# untitled.net
KiCad netlist of a schematic drawn in EAGLE
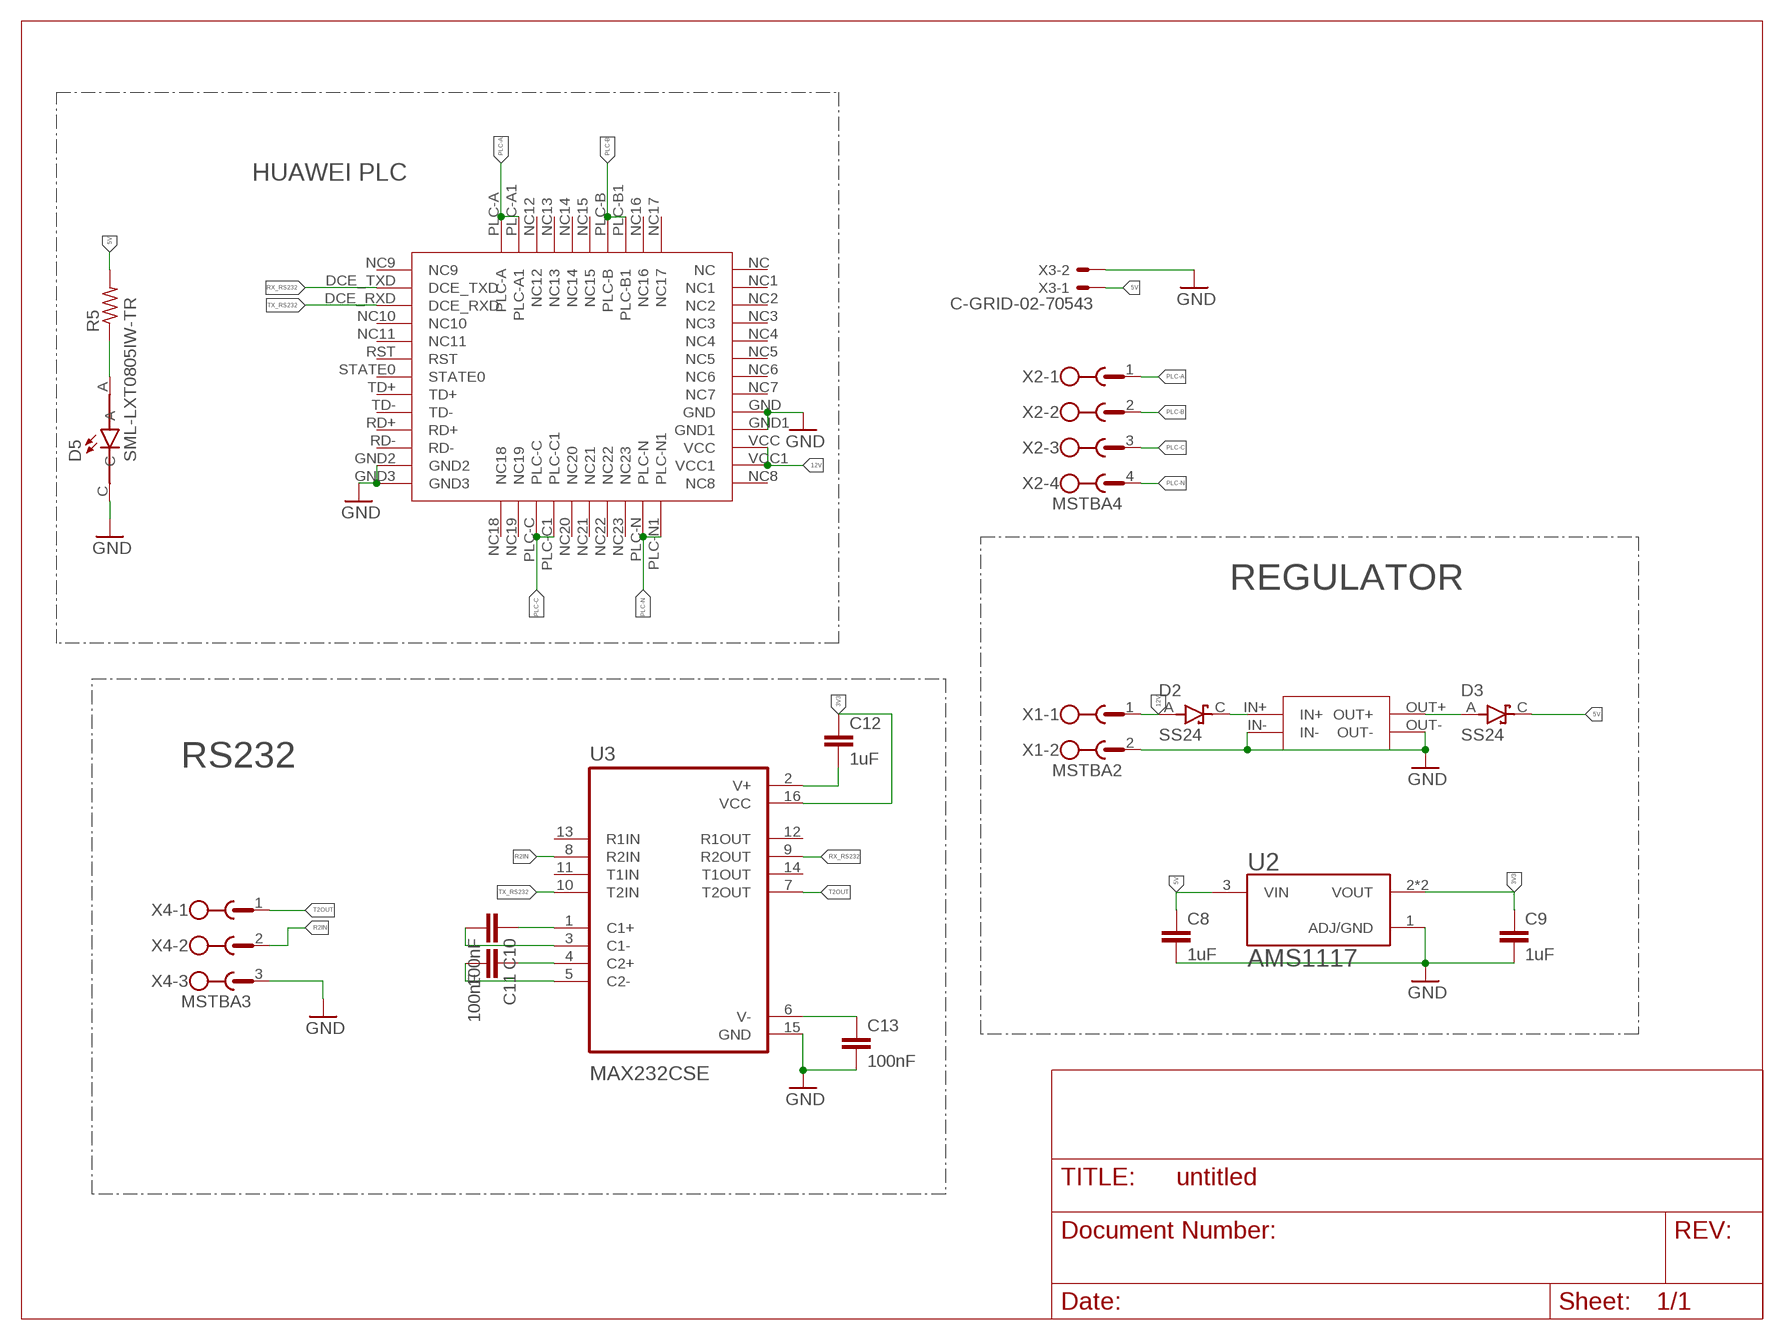
[diagram p0: schematic, sheet 1]

(export (version "E")
  (design (tool "Eeschema 10.0.6"))
  (components
    (comp (ref "C8")
      (value "1uF")
      (footprint "eagle-import:C0805K")
      (libsource (lib "eagle-import") (part "C-EUC0805K"))
    )
    (comp (ref "C9")
      (value "1uF")
      (footprint "eagle-import:C0805K")
      (libsource (lib "eagle-import") (part "C-EUC0805K"))
    )
    (comp (ref "C10")
      (value "100nF")
      (footprint "eagle-import:C0805K")
      (libsource (lib "eagle-import") (part "C-EUC0805K"))
    )
    (comp (ref "C11")
      (value "100nF")
      (footprint "eagle-import:C0805K")
      (libsource (lib "eagle-import") (part "C-EUC0805K"))
    )
    (comp (ref "C12")
      (value "1uF")
      (footprint "eagle-import:C0805K")
      (libsource (lib "eagle-import") (part "C-EUC0805K"))
    )
    (comp (ref "C13")
      (value "100nF")
      (footprint "eagle-import:C0805K")
      (libsource (lib "eagle-import") (part "C-EUC0805K"))
    )
    (comp (ref "D2")
      (value "SS24")
      (footprint "eagle-import:DIOM5336X265N")
      (fields (field (name "MF") "ON Semiconductor"))
      (libsource (lib "eagle-import") (part "SS24"))
    )
    (comp (ref "D3")
      (value "SS24")
      (footprint "eagle-import:DIOM5336X265N")
      (fields (field (name "MF") "ON Semiconductor"))
      (libsource (lib "eagle-import") (part "SS24"))
    )
    (comp (ref "D5")
      (value "SML-LXT0805IW-TR")
      (footprint "eagle-import:LEDC2012X120N")
      (fields (field (name "MF") "Lumex Opto/Components"))
      (libsource (lib "eagle-import") (part "SML-LXT0805IW-TR"))
    )
    (comp (ref "HUAWEI-PLC1")
      (value "HUAWEI-PLC")
      (footprint "eagle-import:HUAWEI-PLC")
      (libsource (lib "eagle-import") (part "HUAWEI-PLC"))
    )
    (comp (ref "MINI1")
      (value "MINI560")
      (footprint "eagle-import:MINI560")
      (libsource (lib "eagle-import") (part "MINI560"))
    )
    (comp (ref "R5")
      (value "R-US_M0805")
      (footprint "eagle-import:M0805")
      (libsource (lib "eagle-import") (part "R-US_M0805"))
    )
    (comp (ref "U2")
      (value "AMS1117")
      (footprint "eagle-import:SOT229P700X180-4N")
      (fields (field (name "MF") "Advanced Monolithic Systems"))
      (libsource (lib "eagle-import") (part "AMS1117"))
    )
    (comp (ref "U3")
      (value "MAX232CSE")
      (footprint "eagle-import:SOIC127P600X175-16N")
      (fields (field (name "MF") "Maxim Integrated"))
      (libsource (lib "eagle-import") (part "MAX232CSE"))
    )
    (comp (ref "X1")
      (value "MSTBA2")
      (footprint "eagle-import:MSTBA2")
      (fields (field (name "MF") "FARNELL") (field (name "MPN") "1757242"))
      (libsource (lib "eagle-import") (part "MSTBA2"))
    )
    (comp (ref "X2")
      (value "MSTBA4")
      (footprint "eagle-import:MSTBA4")
      (fields (field (name "MF") "FARNELL") (field (name "MPN") "1757268"))
      (libsource (lib "eagle-import") (part "MSTBA4"))
    )
    (comp (ref "X3")
      (value "C-GRID-02-70543")
      (footprint "eagle-import:70543-02")
      (fields (field (name "MF") "MOLEX"))
      (libsource (lib "eagle-import") (part "C-GRID-02-70543"))
    )
    (comp (ref "X4")
      (value "MSTBA3")
      (footprint "eagle-import:MSTBA3")
      (fields (field (name "MF") "FARNELL") (field (name "MPN") "1757255"))
      (libsource (lib "eagle-import") (part "MSTBA3"))
    )
  )
  (nets
    (net (code "1") (name "3V3") (class "Default")
      (node (ref "C12") (pin "1") (pinfunction "1_1") (pintype "passive"))
      (node (ref "C9") (pin "1") (pinfunction "1_1") (pintype "passive"))
      (node (ref "U2") (pin "2") (pinfunction "VOUT_2") (pintype "output"))
      (node (ref "U2") (pin "4") (pinfunction "VOUT_4") (pintype "output"))
      (node (ref "U3") (pin "16") (pinfunction "VCC_16") (pintype "power_in"))
    )
    (net (code "2") (name "5V") (class "Default")
      (node (ref "C8") (pin "1") (pinfunction "1_1") (pintype "passive"))
      (node (ref "D3") (pin "C") (pinfunction "K_C") (pintype "passive"))
      (node (ref "R5") (pin "2") (pinfunction "2_2") (pintype "passive"))
      (node (ref "U2") (pin "3") (pinfunction "VIN_3") (pintype "input"))
      (node (ref "X3") (pin "1") (pinfunction "S_1") (pintype "passive"))
    )
    (net (code "3") (name "12V") (class "Default")
      (node (ref "D2") (pin "A") (pinfunction "A_A") (pintype "passive"))
      (node (ref "HUAWEI-PLC1") (pin "VCC") (pinfunction "VCC_VCC") (pintype "bidirectional"))
      (node (ref "HUAWEI-PLC1") (pin "VCC1") (pinfunction "VCC1_VCC1") (pintype "bidirectional"))
      (node (ref "X1") (pin "1") (pinfunction "1_1") (pintype "passive"))
    )
    (net (code "4") (name "GND") (class "Default")
      (node (ref "C13") (pin "2") (pinfunction "2_2") (pintype "passive"))
      (node (ref "C8") (pin "2") (pinfunction "2_2") (pintype "passive"))
      (node (ref "C9") (pin "2") (pinfunction "2_2") (pintype "passive"))
      (node (ref "D5") (pin "C") (pinfunction "C_C") (pintype "passive"))
      (node (ref "HUAWEI-PLC1") (pin "GND") (pinfunction "GND_GND") (pintype "bidirectional"))
      (node (ref "HUAWEI-PLC1") (pin "GND1") (pinfunction "GND1_GND1") (pintype "bidirectional"))
      (node (ref "HUAWEI-PLC1") (pin "GND2") (pinfunction "GND2_GND2") (pintype "bidirectional"))
      (node (ref "HUAWEI-PLC1") (pin "GND3") (pinfunction "GND3_GND3") (pintype "bidirectional"))
      (node (ref "MINI1") (pin "IN-") (pinfunction "IN-_IN-") (pintype "bidirectional"))
      (node (ref "MINI1") (pin "OUT-") (pinfunction "OUT-_OUT-") (pintype "bidirectional"))
      (node (ref "U2") (pin "1") (pinfunction "ADJ/GND_1") (pintype "power_in"))
      (node (ref "U3") (pin "15") (pinfunction "GND_15") (pintype "power_in"))
      (node (ref "X1") (pin "2") (pinfunction "1_2") (pintype "passive"))
      (node (ref "X3") (pin "2") (pinfunction "S_2") (pintype "passive"))
      (node (ref "X4") (pin "3") (pinfunction "1_3") (pintype "passive"))
    )
    (net (code "5") (name "Net-(D2-K)") (class "Default")
      (node (ref "D2") (pin "C") (pinfunction "K_C") (pintype "passive"))
      (node (ref "MINI1") (pin "IN+") (pinfunction "IN+_IN+") (pintype "bidirectional"))
    )
    (net (code "6") (name "Net-(D3-PadA)") (class "Default")
      (node (ref "D3") (pin "A") (pinfunction "A_A") (pintype "passive"))
      (node (ref "MINI1") (pin "OUT+") (pinfunction "OUT+_OUT+") (pintype "bidirectional"))
    )
    (net (code "7") (name "Net-(D5-PadA)") (class "Default")
      (node (ref "D5") (pin "A") (pinfunction "A_A") (pintype "passive"))
      (node (ref "R5") (pin "1") (pinfunction "1_1") (pintype "passive"))
    )
    (net (code "8") (name "Net-(U3-C1+)") (class "Default")
      (node (ref "C10") (pin "1") (pinfunction "1_1") (pintype "passive"))
      (node (ref "U3") (pin "1") (pinfunction "C1+_1") (pintype "bidirectional"))
    )
    (net (code "9") (name "Net-(U3-C1-)") (class "Default")
      (node (ref "C10") (pin "2") (pinfunction "2_2") (pintype "passive"))
      (node (ref "U3") (pin "3") (pinfunction "C1-_3") (pintype "bidirectional"))
    )
    (net (code "10") (name "Net-(U3-C2+)") (class "Default")
      (node (ref "C11") (pin "1") (pinfunction "1_1") (pintype "passive"))
      (node (ref "U3") (pin "4") (pinfunction "C2+_4") (pintype "bidirectional"))
    )
    (net (code "11") (name "Net-(U3-C2-)") (class "Default")
      (node (ref "C11") (pin "2") (pinfunction "2_2") (pintype "passive"))
      (node (ref "U3") (pin "5") (pinfunction "C2-_5") (pintype "bidirectional"))
    )
    (net (code "12") (name "Net-(U3-V+)") (class "Default")
      (node (ref "C12") (pin "2") (pinfunction "2_2") (pintype "passive"))
      (node (ref "U3") (pin "2") (pinfunction "V+_2") (pintype "power_in"))
    )
    (net (code "13") (name "Net-(U3-V-)") (class "Default")
      (node (ref "C13") (pin "1") (pinfunction "1_1") (pintype "passive"))
      (node (ref "U3") (pin "6") (pinfunction "V-_6") (pintype "power_in"))
    )
    (net (code "14") (name "PLC-A") (class "Default")
      (node (ref "HUAWEI-PLC1") (pin "PLC-A") (pinfunction "PLC-A_PLC-A") (pintype "bidirectional"))
      (node (ref "HUAWEI-PLC1") (pin "PLC-A1") (pinfunction "PLC-A1_PLC-A1") (pintype "bidirectional"))
      (node (ref "X2") (pin "1") (pinfunction "1_1") (pintype "passive"))
    )
    (net (code "15") (name "PLC-B") (class "Default")
      (node (ref "HUAWEI-PLC1") (pin "PLC-B") (pinfunction "PLC-B_PLC-B") (pintype "bidirectional"))
      (node (ref "HUAWEI-PLC1") (pin "PLC-B1") (pinfunction "PLC-B1_PLC-B1") (pintype "bidirectional"))
      (node (ref "X2") (pin "2") (pinfunction "1_2") (pintype "passive"))
    )
    (net (code "16") (name "PLC-C") (class "Default")
      (node (ref "HUAWEI-PLC1") (pin "PLC-C") (pinfunction "PLC-C_PLC-C") (pintype "bidirectional"))
      (node (ref "HUAWEI-PLC1") (pin "PLC-C1") (pinfunction "PLC-C1_PLC-C1") (pintype "bidirectional"))
      (node (ref "X2") (pin "3") (pinfunction "1_3") (pintype "passive"))
    )
    (net (code "17") (name "PLC-N") (class "Default")
      (node (ref "HUAWEI-PLC1") (pin "PLC-N") (pinfunction "PLC-N_PLC-N") (pintype "bidirectional"))
      (node (ref "HUAWEI-PLC1") (pin "PLC-N1") (pinfunction "PLC-N1_PLC-N1") (pintype "bidirectional"))
      (node (ref "X2") (pin "4") (pinfunction "1_4") (pintype "passive"))
    )
    (net (code "18") (name "R2IN") (class "Default")
      (node (ref "U3") (pin "8") (pinfunction "R2IN_8") (pintype "input"))
      (node (ref "X4") (pin "2") (pinfunction "1_2") (pintype "passive"))
    )
    (net (code "19") (name "RX_RS232") (class "Default")
      (node (ref "HUAWEI-PLC1") (pin "DCE_TXD") (pinfunction "DCE_TXD_DCE_TXD") (pintype "bidirectional"))
      (node (ref "U3") (pin "9") (pinfunction "R2OUT_9") (pintype "output"))
    )
    (net (code "20") (name "T2OUT") (class "Default")
      (node (ref "U3") (pin "7") (pinfunction "T2OUT_7") (pintype "output"))
      (node (ref "X4") (pin "1") (pinfunction "1_1") (pintype "passive"))
    )
    (net (code "21") (name "TX_RS232") (class "Default")
      (node (ref "HUAWEI-PLC1") (pin "DCE_RXD") (pinfunction "DCE_RXD_DCE_RXD") (pintype "bidirectional"))
      (node (ref "U3") (pin "10") (pinfunction "T2IN_10") (pintype "input"))
    )
    (net (code "22") (name "unconnected-(HUAWEI-PLC1-PadNC)") (class "Default")
      (node (ref "HUAWEI-PLC1") (pin "NC") (pinfunction "NC_NC") (pintype "bidirectional"))
    )
    (net (code "23") (name "unconnected-(HUAWEI-PLC1-PadNC1)") (class "Default")
      (node (ref "HUAWEI-PLC1") (pin "NC1") (pinfunction "NC1_NC1") (pintype "bidirectional"))
    )
    (net (code "24") (name "unconnected-(HUAWEI-PLC1-PadNC2)") (class "Default")
      (node (ref "HUAWEI-PLC1") (pin "NC2") (pinfunction "NC2_NC2") (pintype "bidirectional"))
    )
    (net (code "25") (name "unconnected-(HUAWEI-PLC1-PadNC3)") (class "Default")
      (node (ref "HUAWEI-PLC1") (pin "NC3") (pinfunction "NC3_NC3") (pintype "bidirectional"))
    )
    (net (code "26") (name "unconnected-(HUAWEI-PLC1-PadNC4)") (class "Default")
      (node (ref "HUAWEI-PLC1") (pin "NC4") (pinfunction "NC4_NC4") (pintype "bidirectional"))
    )
    (net (code "27") (name "unconnected-(HUAWEI-PLC1-PadNC5)") (class "Default")
      (node (ref "HUAWEI-PLC1") (pin "NC5") (pinfunction "NC5_NC5") (pintype "bidirectional"))
    )
    (net (code "28") (name "unconnected-(HUAWEI-PLC1-PadNC6)") (class "Default")
      (node (ref "HUAWEI-PLC1") (pin "NC6") (pinfunction "NC6_NC6") (pintype "bidirectional"))
    )
    (net (code "29") (name "unconnected-(HUAWEI-PLC1-PadNC7)") (class "Default")
      (node (ref "HUAWEI-PLC1") (pin "NC7") (pinfunction "NC7_NC7") (pintype "bidirectional"))
    )
    (net (code "30") (name "unconnected-(HUAWEI-PLC1-PadNC8)") (class "Default")
      (node (ref "HUAWEI-PLC1") (pin "NC8") (pinfunction "NC8_NC8") (pintype "bidirectional"))
    )
    (net (code "31") (name "unconnected-(HUAWEI-PLC1-PadNC9)") (class "Default")
      (node (ref "HUAWEI-PLC1") (pin "NC9") (pinfunction "NC9_NC9") (pintype "bidirectional"))
    )
    (net (code "32") (name "unconnected-(HUAWEI-PLC1-PadNC10)") (class "Default")
      (node (ref "HUAWEI-PLC1") (pin "NC10") (pinfunction "NC10_NC10") (pintype "bidirectional"))
    )
    (net (code "33") (name "unconnected-(HUAWEI-PLC1-PadNC11)") (class "Default")
      (node (ref "HUAWEI-PLC1") (pin "NC11") (pinfunction "NC11_NC11") (pintype "bidirectional"))
    )
    (net (code "34") (name "unconnected-(HUAWEI-PLC1-PadNC12)") (class "Default")
      (node (ref "HUAWEI-PLC1") (pin "NC12") (pinfunction "NC12_NC12") (pintype "bidirectional"))
    )
    (net (code "35") (name "unconnected-(HUAWEI-PLC1-PadNC13)") (class "Default")
      (node (ref "HUAWEI-PLC1") (pin "NC13") (pinfunction "NC13_NC13") (pintype "bidirectional"))
    )
    (net (code "36") (name "unconnected-(HUAWEI-PLC1-PadNC14)") (class "Default")
      (node (ref "HUAWEI-PLC1") (pin "NC14") (pinfunction "NC14_NC14") (pintype "bidirectional"))
    )
    (net (code "37") (name "unconnected-(HUAWEI-PLC1-PadNC15)") (class "Default")
      (node (ref "HUAWEI-PLC1") (pin "NC15") (pinfunction "NC15_NC15") (pintype "bidirectional"))
    )
    (net (code "38") (name "unconnected-(HUAWEI-PLC1-PadNC16)") (class "Default")
      (node (ref "HUAWEI-PLC1") (pin "NC16") (pinfunction "NC16_NC16") (pintype "bidirectional"))
    )
    (net (code "39") (name "unconnected-(HUAWEI-PLC1-PadNC17)") (class "Default")
      (node (ref "HUAWEI-PLC1") (pin "NC17") (pinfunction "NC17_NC17") (pintype "bidirectional"))
    )
    (net (code "40") (name "unconnected-(HUAWEI-PLC1-PadNC18)") (class "Default")
      (node (ref "HUAWEI-PLC1") (pin "NC18") (pinfunction "NC18_NC18") (pintype "bidirectional"))
    )
    (net (code "41") (name "unconnected-(HUAWEI-PLC1-PadNC19)") (class "Default")
      (node (ref "HUAWEI-PLC1") (pin "NC19") (pinfunction "NC19_NC19") (pintype "bidirectional"))
    )
    (net (code "42") (name "unconnected-(HUAWEI-PLC1-PadNC20)") (class "Default")
      (node (ref "HUAWEI-PLC1") (pin "NC20") (pinfunction "NC20_NC20") (pintype "bidirectional"))
    )
    (net (code "43") (name "unconnected-(HUAWEI-PLC1-PadNC21)") (class "Default")
      (node (ref "HUAWEI-PLC1") (pin "NC21") (pinfunction "NC21_NC21") (pintype "bidirectional"))
    )
    (net (code "44") (name "unconnected-(HUAWEI-PLC1-PadNC22)") (class "Default")
      (node (ref "HUAWEI-PLC1") (pin "NC22") (pinfunction "NC22_NC22") (pintype "bidirectional"))
    )
    (net (code "45") (name "unconnected-(HUAWEI-PLC1-PadNC23)") (class "Default")
      (node (ref "HUAWEI-PLC1") (pin "NC23") (pinfunction "NC23_NC23") (pintype "bidirectional"))
    )
    (net (code "46") (name "unconnected-(HUAWEI-PLC1-PadRD+)") (class "Default")
      (node (ref "HUAWEI-PLC1") (pin "RD+") (pinfunction "RD+_RD+") (pintype "bidirectional"))
    )
    (net (code "47") (name "unconnected-(HUAWEI-PLC1-PadRD-)") (class "Default")
      (node (ref "HUAWEI-PLC1") (pin "RD-") (pinfunction "RD-_RD-") (pintype "bidirectional"))
    )
    (net (code "48") (name "unconnected-(HUAWEI-PLC1-PadRST)") (class "Default")
      (node (ref "HUAWEI-PLC1") (pin "RST") (pinfunction "RST_RST") (pintype "bidirectional"))
    )
    (net (code "49") (name "unconnected-(HUAWEI-PLC1-PadSTATE0)") (class "Default")
      (node (ref "HUAWEI-PLC1") (pin "STATE0") (pinfunction "STATE0_STATE0") (pintype "bidirectional"))
    )
    (net (code "50") (name "unconnected-(HUAWEI-PLC1-PadTD+)") (class "Default")
      (node (ref "HUAWEI-PLC1") (pin "TD+") (pinfunction "TD+_TD+") (pintype "bidirectional"))
    )
    (net (code "51") (name "unconnected-(HUAWEI-PLC1-PadTD-)") (class "Default")
      (node (ref "HUAWEI-PLC1") (pin "TD-") (pinfunction "TD-_TD-") (pintype "bidirectional"))
    )
    (net (code "52") (name "unconnected-(U3-R1IN-Pad13)") (class "Default")
      (node (ref "U3") (pin "13") (pinfunction "R1IN_13") (pintype "input"))
    )
    (net (code "53") (name "unconnected-(U3-R1OUT-Pad12)") (class "Default")
      (node (ref "U3") (pin "12") (pinfunction "R1OUT_12") (pintype "output"))
    )
    (net (code "54") (name "unconnected-(U3-T1IN-Pad11)") (class "Default")
      (node (ref "U3") (pin "11") (pinfunction "T1IN_11") (pintype "input"))
    )
    (net (code "55") (name "unconnected-(U3-T1OUT-Pad14)") (class "Default")
      (node (ref "U3") (pin "14") (pinfunction "T1OUT_14") (pintype "output"))
    )
  )
)
